# v1_0.net
KiCad netlist of a schematic drawn in Altium Designer
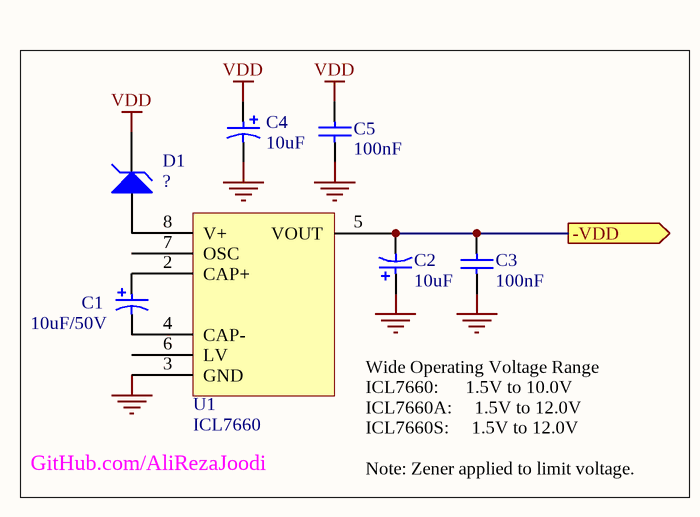
[diagram p0: v1.0.SchDoc]

(export (version "E")
  (design (tool "Eeschema 10.0.6"))
  (components
    (comp (ref "C1")
      (value "10uF/50V")
      (footprint "C_THD_EL_(P2.54-D6-H11)")
      (description "Capacitor, Electrolytic")
      (libsource (lib "Passive") (part "Capacitor_Electrolytic"))
    )
    (comp (ref "C2")
      (value "10uF")
      (footprint "C_THD_EL_(P2.54-D6-H11)")
      (description "Capacitor, Electrolytic")
      (libsource (lib "Passive") (part "Capacitor_Electrolytic"))
    )
    (comp (ref "C3")
      (value "100nF")
      (footprint "C_THD_CER_(P2.54-D3.5-T1.5)")
      (description "Capacitor, Ceramic Multilayer")
      (libsource (lib "Passive") (part "Capacitor_Ceramic"))
    )
    (comp (ref "C4")
      (value "10uF")
      (footprint "C_THD_EL_(P2.54-D6-H11)")
      (description "Capacitor, Electrolytic")
      (libsource (lib "Passive") (part "Capacitor_Electrolytic"))
    )
    (comp (ref "C5")
      (value "100nF")
      (footprint "C_THD_CER_(P2.54-D3.5-T1.5)")
      (description "Capacitor, Ceramic Multilayer")
      (libsource (lib "Passive") (part "Capacitor_Ceramic"))
    )
    (comp (ref "D1")
      (value "?")
      (footprint "DIODE0.4_Glass")
      (description "Zener Diode")
      (fields (field (name "MANUFACTURER") "Generic Components") (field (name "PUBLISHER") "Altium Limited"))
      (libsource (lib "Miscellaneous Devices") (part "D Zener"))
    )
    (comp (ref "U1") (value "ICL7660") (footprint "DIP_8") (libsource (lib "Other_Myself") (part "ICL7660")))
  )
  (nets
    (net (code "1") (name "/-VDD") (class "Default")
      (node (ref "C2") (pin "2") (pinfunction "2_2") (pintype "passive"))
      (node (ref "C3") (pin "2") (pinfunction "2_2") (pintype "passive"))
      (node (ref "U1") (pin "5") (pinfunction "VOUT_5") (pintype "passive"))
    )
    (net (code "2") (name "GND") (class "Default")
      (node (ref "C2") (pin "1") (pinfunction "1_1") (pintype "passive"))
      (node (ref "C3") (pin "1") (pinfunction "1_1") (pintype "passive"))
      (node (ref "C4") (pin "2") (pinfunction "2_2") (pintype "passive"))
      (node (ref "C5") (pin "2") (pinfunction "2_2") (pintype "passive"))
      (node (ref "U1") (pin "3") (pinfunction "GND_3") (pintype "passive"))
    )
    (net (code "3") (name "Net-(D1-A)") (class "Default")
      (node (ref "D1") (pin "1") (pinfunction "A_1") (pintype "passive"))
      (node (ref "U1") (pin "8") (pinfunction "V+_8") (pintype "passive"))
    )
    (net (code "4") (name "Net-(U1-CAP+)") (class "Default")
      (node (ref "C1") (pin "1") (pinfunction "1_1") (pintype "passive"))
      (node (ref "U1") (pin "2") (pinfunction "CAP+_2") (pintype "passive"))
    )
    (net (code "5") (name "Net-(U1-CAP-)") (class "Default")
      (node (ref "C1") (pin "2") (pinfunction "2_2") (pintype "passive"))
      (node (ref "U1") (pin "4") (pinfunction "CAP-_4") (pintype "passive"))
    )
    (net (code "6") (name "VDD") (class "Default")
      (node (ref "C4") (pin "1") (pinfunction "1_1") (pintype "passive"))
      (node (ref "C5") (pin "1") (pinfunction "1_1") (pintype "passive"))
      (node (ref "D1") (pin "2") (pinfunction "K_2") (pintype "passive"))
    )
    (net (code "7") (name "unconnected-(U1-LV-Pad6)") (class "Default")
      (node (ref "U1") (pin "6") (pinfunction "LV_6") (pintype "passive"))
    )
    (net (code "8") (name "unconnected-(U1-OSC-Pad7)") (class "Default")
      (node (ref "U1") (pin "7") (pinfunction "OSC_7") (pintype "passive"))
    )
  )
)
